# course_project_bulid.net
KiCad netlist of a schematic drawn in EasyEDA Pro
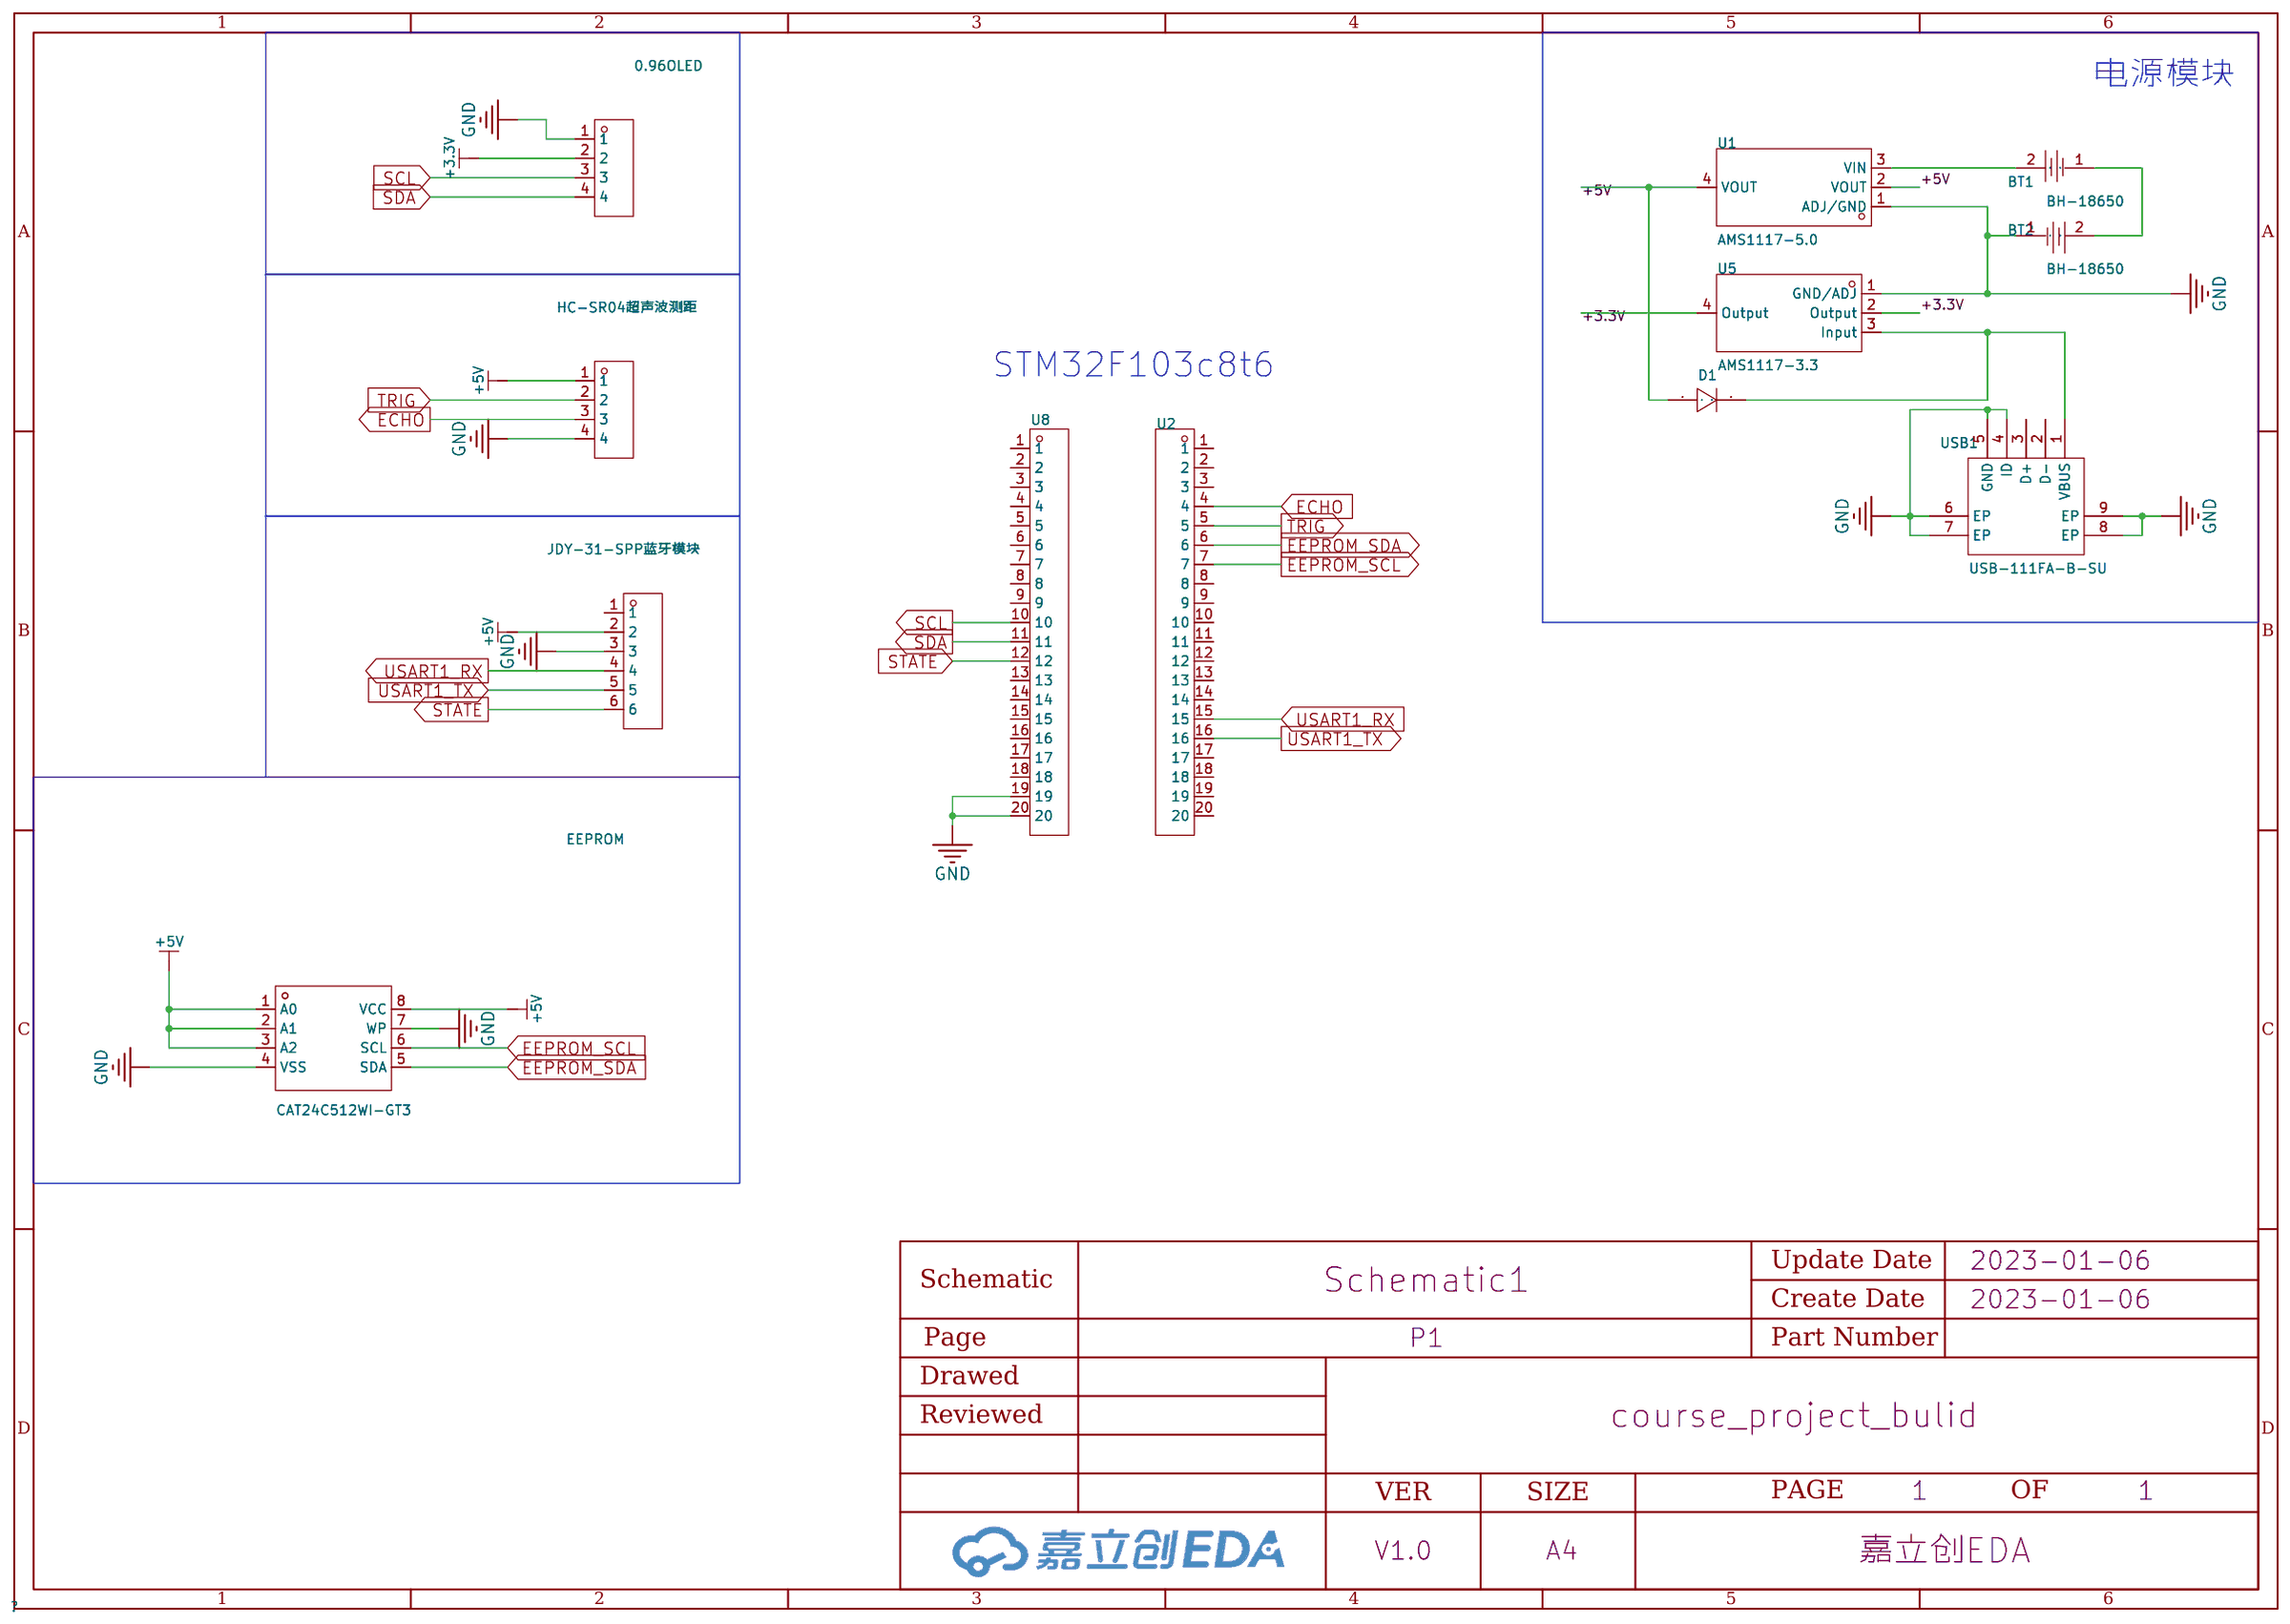
[diagram p0: schematic sheet]

(export (version "E")
  (design (tool "Eeschema 10.0.6"))
  (components
    (comp (ref "BT1")
      (value "BH-18650")
      (footprint "easyedapro:BATTERY-SMD_18650-1S-L77.1-W20.7-1")
      (fields (field (name "Manufacturer") "MYOUNG(美阳)"))
      (libsource (lib "easyedapro") (part "BH-18650-B1BA002"))
    )
    (comp (ref "BT2")
      (value "BH-18650")
      (footprint "easyedapro:BATTERY-SMD_18650-1S-L77.1-W20.7-1")
      (fields (field (name "Manufacturer") "MYOUNG(美阳)"))
      (libsource (lib "easyedapro") (part "BH-18650-B1BA002"))
    )
    (comp (ref "D1")
      (value "1N4148WS")
      (footprint "easyedapro:SOD-323_L1.8-W1.3-LS2.5-RD")
      (fields (field (name "Manufacturer") "CJ(江苏长电/长晶)"))
      (libsource (lib "easyedapro") (part "1N4148WS T4"))
    )
    (comp (ref "EEPROM")
      (value "CAT24C512WI-GT3")
      (footprint "easyedapro:SOIC-8_L4.9-W3.9-P1.27-LS6.0-BL")
      (fields (field (name "Manufacturer") "onsemi(安森美)"))
      (libsource (lib "easyedapro") (part "CAT24C512WI-GT3"))
    )
    (comp (ref "HC-SR04超声波测距")
      (value "PM254-1-04-W-8.5")
      (footprint "easyedapro:HDR-TH_4P-P2.54-H-F-W10.0-N")
      (fields (field (name "Manufacturer") "HCTL(华灿天禄)"))
      (libsource (lib "easyedapro") (part "PM254-1-04-W-8.5"))
    )
    (comp (ref "JDY-31-SPP蓝牙模块")
      (value "PM254-1-06-W-8.5")
      (footprint "easyedapro:HDR-TH_6P-P2.54-H-F-W10.0-N")
      (fields (field (name "Manufacturer") "HCTL(华灿天禄)"))
      (libsource (lib "easyedapro") (part "PM254-1-06-W-8.5"))
    )
    (comp (ref "U1")
      (value "AMS1117-5.0")
      (footprint "easyedapro:SOT-223-3_L6.5-W3.4-P2.30-LS7.0-BR")
      (fields (field (name "Manufacturer") "WPMtek(维攀微)"))
      (libsource (lib "easyedapro") (part "AMS1117-5.0_C2909825"))
    )
    (comp (ref "U2")
      (value "X5511FV-20-C30D97-0970")
      (footprint "easyedapro:HDR-TH_20P-P2.54-V-F")
      (fields (field (name "Manufacturer") "XKB Connectivity(中国星坤)"))
      (libsource (lib "easyedapro") (part "X5511FV-20-C30D97-0970"))
    )
    (comp (ref "U3")
      (value "0.96OLED")
      (footprint "easyedapro:HDR-TH_4P-P2.54-V-F")
      (fields (field (name "Manufacturer") "CJT(长江连接器)"))
      (libsource (lib "easyedapro") (part "A2541HWV-4P_C5176037"))
    )
    (comp (ref "U5")
      (value "AMS1117-3.3")
      (footprint "easyedapro:SOT-223-4_L6.5-W3.5-P2.30-LS7.0-BR")
      (fields (field (name "Manufacturer") "KEXIN(科信)"))
      (libsource (lib "easyedapro") (part "AMS1117-3.3_C369933"))
    )
    (comp (ref "U8")
      (value "X5511FV-20-C30D97-0970")
      (footprint "easyedapro:HDR-TH_20P-P2.54-V-F")
      (fields (field (name "Manufacturer") "XKB Connectivity(中国星坤)"))
      (libsource (lib "easyedapro") (part "X5511FV-20-C30D97-0970"))
    )
    (comp (ref "USB1")
      (value "USB-111FA-B-SU")
      (footprint "easyedapro:USB-SMD_USB-111FA-B-SU")
      (description "mirco usb连接器 USB-111FA-B-SU B型 5.06*7.5*2")
      (fields (field (name "Manufacturer") "HOOYA(皓宇电子)"))
      (libsource (lib "easyedapro") (part "USB-111FA-B-SU"))
    )
  )
  (nets
    (net (code "1") (name "+3.3V") (class "Default")
      (node (ref "U3") (pin "2") (pinfunction "2_2") (pintype "input"))
      (node (ref "U5") (pin "2") (pinfunction "Output_2") (pintype "input"))
      (node (ref "U5") (pin "4") (pinfunction "Output_4") (pintype "input"))
    )
    (net (code "2") (name "+5V") (class "Default")
      (node (ref "D1") (pin "2") (pinfunction "A_2") (pintype "input"))
      (node (ref "EEPROM") (pin "1") (pinfunction "A0_1") (pintype "input"))
      (node (ref "EEPROM") (pin "2") (pinfunction "A1_2") (pintype "input"))
      (node (ref "EEPROM") (pin "3") (pinfunction "A2_3") (pintype "input"))
      (node (ref "EEPROM") (pin "8") (pinfunction "VCC_8") (pintype "input"))
      (node (ref "HC-SR04超声波测距") (pin "1") (pinfunction "1_1") (pintype "input"))
      (node (ref "JDY-31-SPP蓝牙模块") (pin "2") (pinfunction "2_2") (pintype "input"))
      (node (ref "U1") (pin "2") (pinfunction "VOUT_2") (pintype "input"))
      (node (ref "U1") (pin "4") (pinfunction "VOUT_4") (pintype "input"))
    )
    (net (code "3") (name "ECHO") (class "Default")
      (node (ref "HC-SR04超声波测距") (pin "3") (pinfunction "3_3") (pintype "input"))
      (node (ref "U2") (pin "4") (pinfunction "4_4") (pintype "input"))
    )
    (net (code "4") (name "EEPROM_SCL") (class "Default")
      (node (ref "EEPROM") (pin "6") (pinfunction "SCL_6") (pintype "input"))
      (node (ref "U2") (pin "7") (pinfunction "7_7") (pintype "input"))
    )
    (net (code "5") (name "EEPROM_SDA") (class "Default")
      (node (ref "EEPROM") (pin "5") (pinfunction "SDA_5") (pintype "input"))
      (node (ref "U2") (pin "6") (pinfunction "6_6") (pintype "input"))
    )
    (net (code "6") (name "GND") (class "Default")
      (node (ref "BT2") (pin "1") (pinfunction "1_1") (pintype "input"))
      (node (ref "EEPROM") (pin "4") (pinfunction "VSS_4") (pintype "input"))
      (node (ref "EEPROM") (pin "7") (pinfunction "WP_7") (pintype "input"))
      (node (ref "HC-SR04超声波测距") (pin "4") (pinfunction "4_4") (pintype "input"))
      (node (ref "JDY-31-SPP蓝牙模块") (pin "3") (pinfunction "3_3") (pintype "input"))
      (node (ref "U1") (pin "1") (pinfunction "ADJ/GND_1") (pintype "input"))
      (node (ref "U3") (pin "1") (pinfunction "1_1") (pintype "input"))
      (node (ref "U5") (pin "1") (pinfunction "GND/ADJ_1") (pintype "input"))
      (node (ref "U8") (pin "19") (pinfunction "19_19") (pintype "input"))
      (node (ref "U8") (pin "20") (pinfunction "20_20") (pintype "input"))
      (node (ref "USB1") (pin "4") (pinfunction "ID_4") (pintype "input"))
      (node (ref "USB1") (pin "5") (pinfunction "GND_5") (pintype "input"))
      (node (ref "USB1") (pin "6") (pinfunction "EP_6") (pintype "input"))
      (node (ref "USB1") (pin "7") (pinfunction "EP_7") (pintype "input"))
      (node (ref "USB1") (pin "8") (pinfunction "EP_8") (pintype "input"))
      (node (ref "USB1") (pin "9") (pinfunction "EP_9") (pintype "input"))
    )
    (net (code "7") (name "Net-(BT1-Pad1)") (class "Default")
      (node (ref "BT1") (pin "1") (pinfunction "1_1") (pintype "input"))
      (node (ref "BT2") (pin "2") (pinfunction "2_2") (pintype "input"))
    )
    (net (code "8") (name "Net-(D1-K)") (class "Default")
      (node (ref "D1") (pin "1") (pinfunction "K_1") (pintype "input"))
      (node (ref "U5") (pin "3") (pinfunction "Input_3") (pintype "input"))
      (node (ref "USB1") (pin "1") (pinfunction "VBUS_1") (pintype "input"))
    )
    (net (code "9") (name "Net-(U1-VIN)") (class "Default")
      (node (ref "BT1") (pin "2") (pinfunction "2_2") (pintype "input"))
      (node (ref "U1") (pin "3") (pinfunction "VIN_3") (pintype "input"))
    )
    (net (code "10") (name "SCL") (class "Default")
      (node (ref "U3") (pin "3") (pinfunction "3_3") (pintype "input"))
      (node (ref "U8") (pin "10") (pinfunction "10_10") (pintype "input"))
    )
    (net (code "11") (name "SDA") (class "Default")
      (node (ref "U3") (pin "4") (pinfunction "4_4") (pintype "input"))
      (node (ref "U8") (pin "11") (pinfunction "11_11") (pintype "input"))
    )
    (net (code "12") (name "STATE") (class "Default")
      (node (ref "JDY-31-SPP蓝牙模块") (pin "6") (pinfunction "6_6") (pintype "input"))
      (node (ref "U8") (pin "12") (pinfunction "12_12") (pintype "input"))
    )
    (net (code "13") (name "TRIG") (class "Default")
      (node (ref "HC-SR04超声波测距") (pin "2") (pinfunction "2_2") (pintype "input"))
      (node (ref "U2") (pin "5") (pinfunction "5_5") (pintype "input"))
    )
    (net (code "14") (name "USART1_RX") (class "Default")
      (node (ref "JDY-31-SPP蓝牙模块") (pin "4") (pinfunction "4_4") (pintype "input"))
      (node (ref "U2") (pin "15") (pinfunction "15_15") (pintype "input"))
    )
    (net (code "15") (name "USART1_TX") (class "Default")
      (node (ref "JDY-31-SPP蓝牙模块") (pin "5") (pinfunction "5_5") (pintype "input"))
      (node (ref "U2") (pin "16") (pinfunction "16_16") (pintype "input"))
    )
    (net (code "16") (name "unconnected-(JDY-31-SPP蓝牙模块-Pad1)") (class "Default")
      (node (ref "JDY-31-SPP蓝牙模块") (pin "1") (pinfunction "1_1") (pintype "input"))
    )
    (net (code "17") (name "unconnected-(U2-Pad1)") (class "Default")
      (node (ref "U2") (pin "1") (pinfunction "1_1") (pintype "input"))
    )
    (net (code "18") (name "unconnected-(U2-Pad2)") (class "Default")
      (node (ref "U2") (pin "2") (pinfunction "2_2") (pintype "input"))
    )
    (net (code "19") (name "unconnected-(U2-Pad3)") (class "Default")
      (node (ref "U2") (pin "3") (pinfunction "3_3") (pintype "input"))
    )
    (net (code "20") (name "unconnected-(U2-Pad8)") (class "Default")
      (node (ref "U2") (pin "8") (pinfunction "8_8") (pintype "input"))
    )
    (net (code "21") (name "unconnected-(U2-Pad9)") (class "Default")
      (node (ref "U2") (pin "9") (pinfunction "9_9") (pintype "input"))
    )
    (net (code "22") (name "unconnected-(U2-Pad10)") (class "Default")
      (node (ref "U2") (pin "10") (pinfunction "10_10") (pintype "input"))
    )
    (net (code "23") (name "unconnected-(U2-Pad11)") (class "Default")
      (node (ref "U2") (pin "11") (pinfunction "11_11") (pintype "input"))
    )
    (net (code "24") (name "unconnected-(U2-Pad12)") (class "Default")
      (node (ref "U2") (pin "12") (pinfunction "12_12") (pintype "input"))
    )
    (net (code "25") (name "unconnected-(U2-Pad13)") (class "Default")
      (node (ref "U2") (pin "13") (pinfunction "13_13") (pintype "input"))
    )
    (net (code "26") (name "unconnected-(U2-Pad14)") (class "Default")
      (node (ref "U2") (pin "14") (pinfunction "14_14") (pintype "input"))
    )
    (net (code "27") (name "unconnected-(U2-Pad17)") (class "Default")
      (node (ref "U2") (pin "17") (pinfunction "17_17") (pintype "input"))
    )
    (net (code "28") (name "unconnected-(U2-Pad18)") (class "Default")
      (node (ref "U2") (pin "18") (pinfunction "18_18") (pintype "input"))
    )
    (net (code "29") (name "unconnected-(U2-Pad19)") (class "Default")
      (node (ref "U2") (pin "19") (pinfunction "19_19") (pintype "input"))
    )
    (net (code "30") (name "unconnected-(U2-Pad20)") (class "Default")
      (node (ref "U2") (pin "20") (pinfunction "20_20") (pintype "input"))
    )
    (net (code "31") (name "unconnected-(U8-Pad1)") (class "Default")
      (node (ref "U8") (pin "1") (pinfunction "1_1") (pintype "input"))
    )
    (net (code "32") (name "unconnected-(U8-Pad2)") (class "Default")
      (node (ref "U8") (pin "2") (pinfunction "2_2") (pintype "input"))
    )
    (net (code "33") (name "unconnected-(U8-Pad3)") (class "Default")
      (node (ref "U8") (pin "3") (pinfunction "3_3") (pintype "input"))
    )
    (net (code "34") (name "unconnected-(U8-Pad4)") (class "Default")
      (node (ref "U8") (pin "4") (pinfunction "4_4") (pintype "input"))
    )
    (net (code "35") (name "unconnected-(U8-Pad5)") (class "Default")
      (node (ref "U8") (pin "5") (pinfunction "5_5") (pintype "input"))
    )
    (net (code "36") (name "unconnected-(U8-Pad6)") (class "Default")
      (node (ref "U8") (pin "6") (pinfunction "6_6") (pintype "input"))
    )
    (net (code "37") (name "unconnected-(U8-Pad7)") (class "Default")
      (node (ref "U8") (pin "7") (pinfunction "7_7") (pintype "input"))
    )
    (net (code "38") (name "unconnected-(U8-Pad8)") (class "Default")
      (node (ref "U8") (pin "8") (pinfunction "8_8") (pintype "input"))
    )
    (net (code "39") (name "unconnected-(U8-Pad9)") (class "Default")
      (node (ref "U8") (pin "9") (pinfunction "9_9") (pintype "input"))
    )
    (net (code "40") (name "unconnected-(U8-Pad13)") (class "Default")
      (node (ref "U8") (pin "13") (pinfunction "13_13") (pintype "input"))
    )
    (net (code "41") (name "unconnected-(U8-Pad14)") (class "Default")
      (node (ref "U8") (pin "14") (pinfunction "14_14") (pintype "input"))
    )
    (net (code "42") (name "unconnected-(U8-Pad15)") (class "Default")
      (node (ref "U8") (pin "15") (pinfunction "15_15") (pintype "input"))
    )
    (net (code "43") (name "unconnected-(U8-Pad16)") (class "Default")
      (node (ref "U8") (pin "16") (pinfunction "16_16") (pintype "input"))
    )
    (net (code "44") (name "unconnected-(U8-Pad17)") (class "Default")
      (node (ref "U8") (pin "17") (pinfunction "17_17") (pintype "input"))
    )
    (net (code "45") (name "unconnected-(U8-Pad18)") (class "Default")
      (node (ref "U8") (pin "18") (pinfunction "18_18") (pintype "input"))
    )
    (net (code "46") (name "unconnected-(USB1-D+-Pad3)") (class "Default")
      (node (ref "USB1") (pin "3") (pinfunction "D+_3") (pintype "input"))
    )
    (net (code "47") (name "unconnected-(USB1-D--Pad2)") (class "Default")
      (node (ref "USB1") (pin "2") (pinfunction "D-_2") (pintype "input"))
    )
  )
)
